# secam-perif94.net
KiCad netlist of a schematic drawn in EAGLE
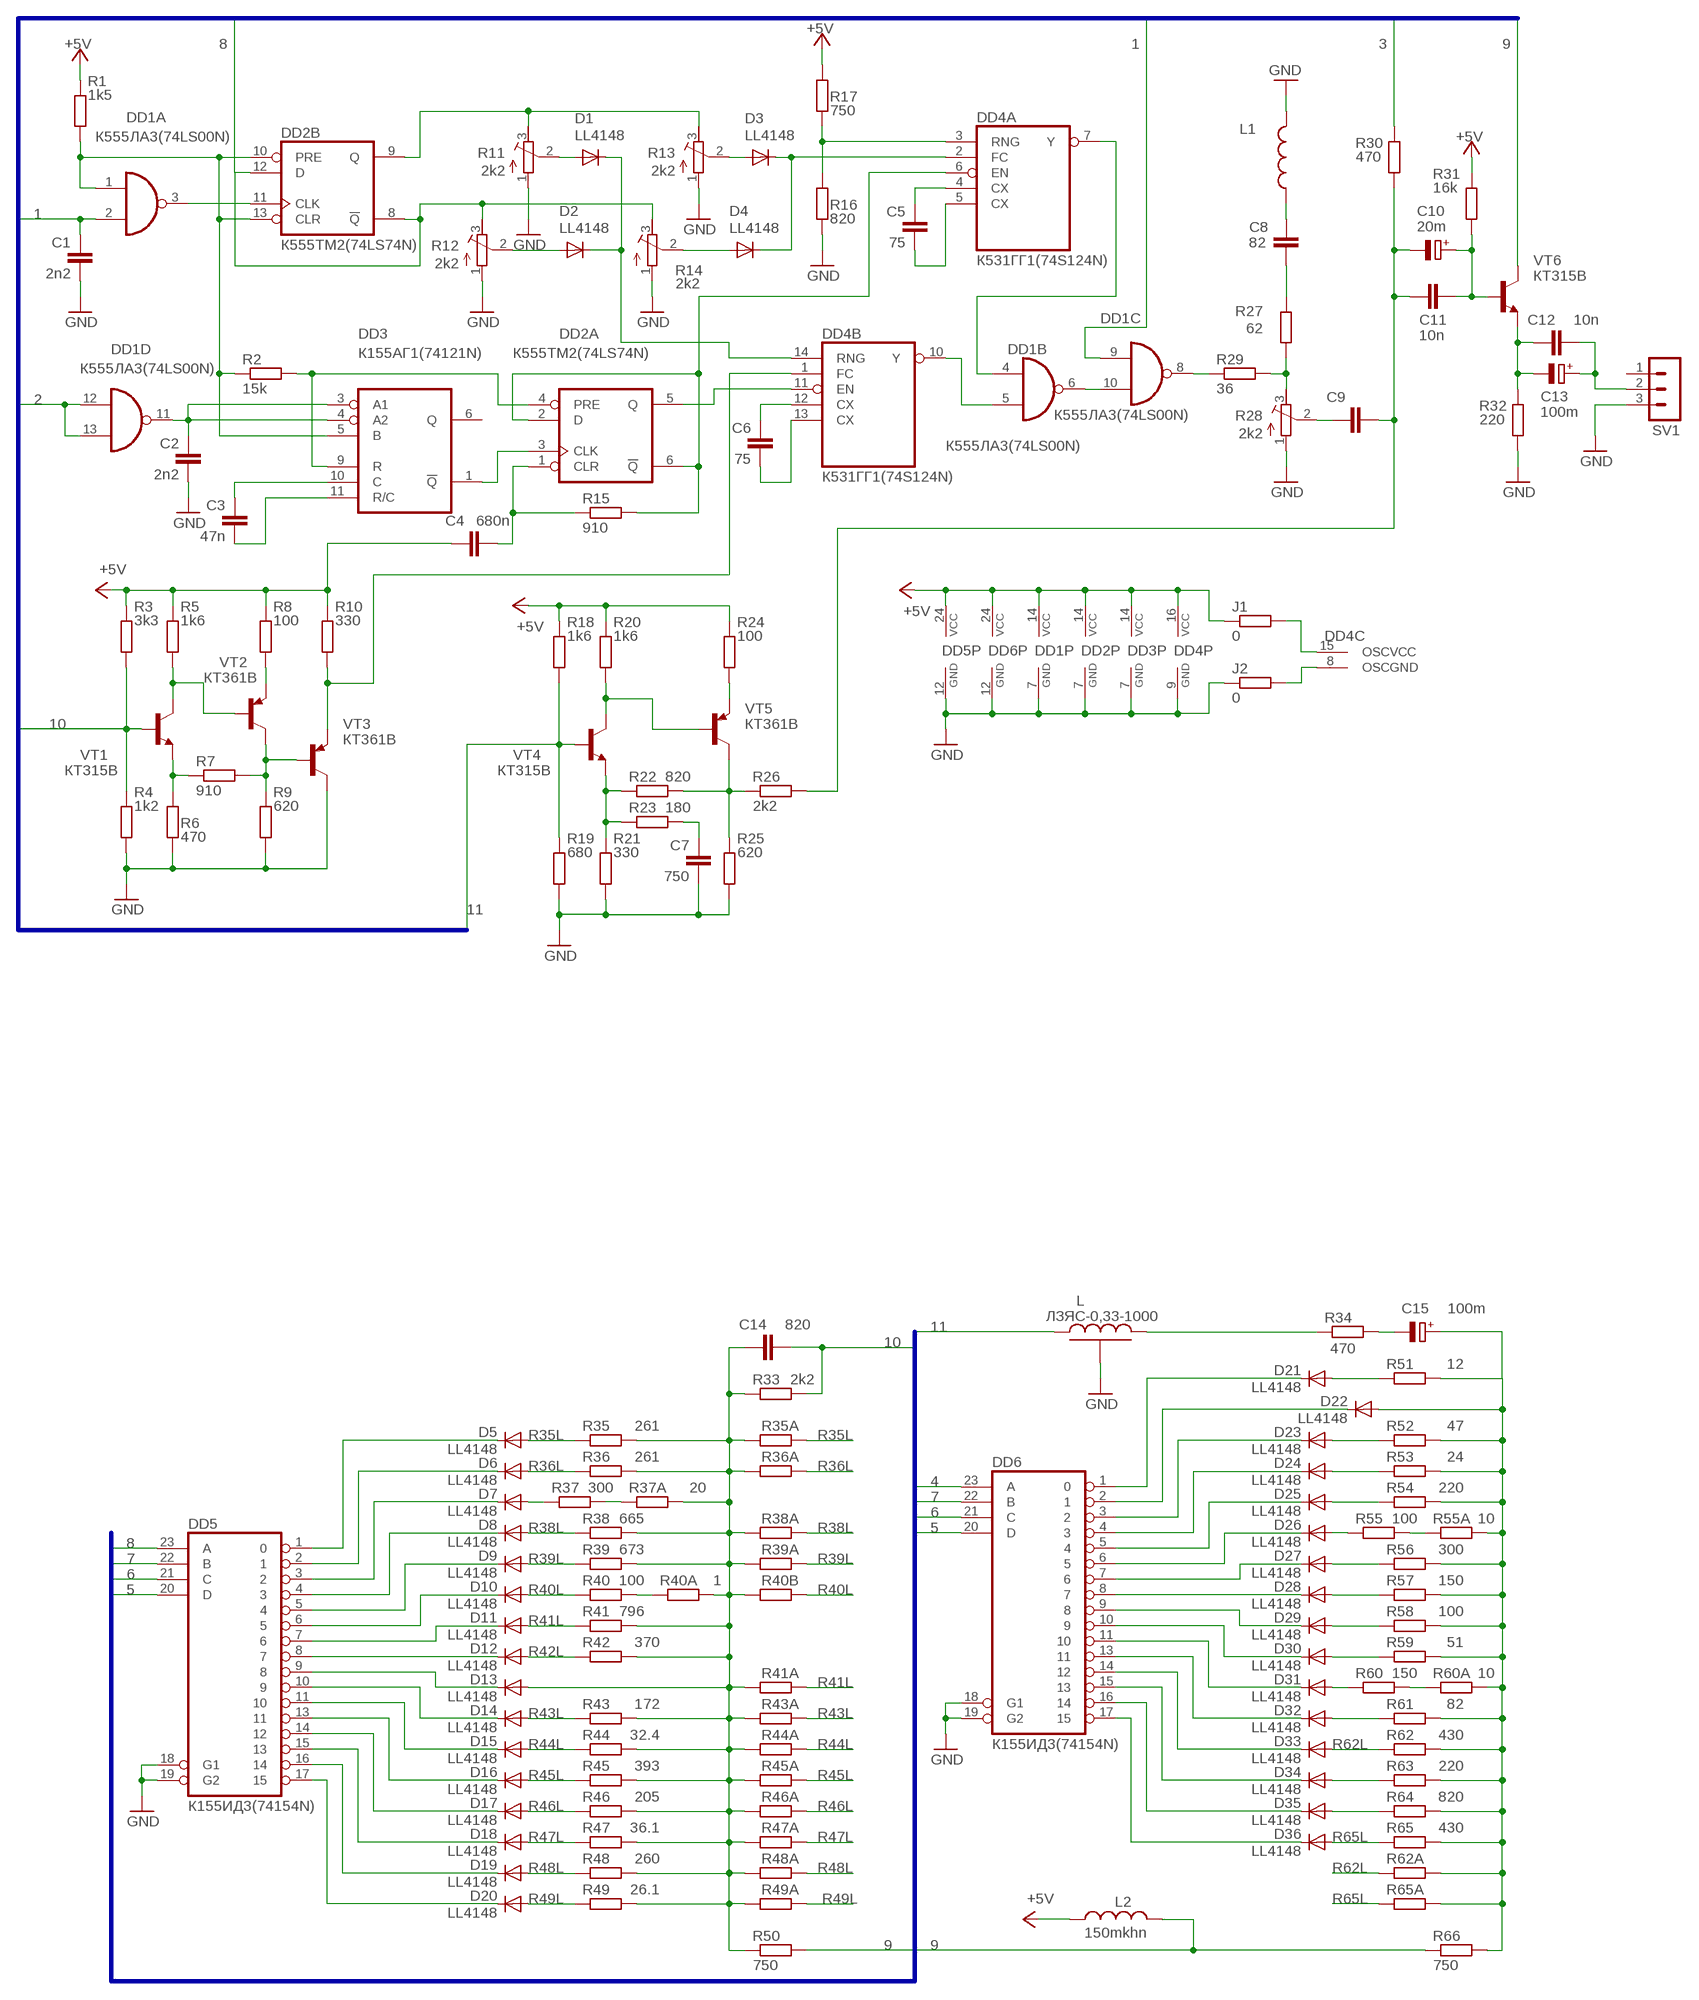
[diagram p0: schematic, sheet 1]

(export (version "E")
  (design (tool "Eeschema 10.0.6"))
  (components
    (comp (ref "C1")
      (value "2n2")
      (footprint "eagle-import:C025-025X050")
      (libsource (lib "eagle-import") (part "C-EU025-025X050"))
    )
    (comp (ref "C2")
      (value "2n2")
      (footprint "eagle-import:C025-025X050")
      (libsource (lib "eagle-import") (part "C-EU025-025X050"))
    )
    (comp (ref "C3")
      (value "47n")
      (footprint "eagle-import:C025-025X050")
      (libsource (lib "eagle-import") (part "C-EU025-025X050"))
    )
    (comp (ref "C4")
      (value "680n")
      (footprint "eagle-import:C025-025X050")
      (libsource (lib "eagle-import") (part "C-EU025-025X050"))
    )
    (comp (ref "C5")
      (value "75")
      (footprint "eagle-import:C025-025X050")
      (libsource (lib "eagle-import") (part "C-EU025-025X050"))
    )
    (comp (ref "C6")
      (value "75")
      (footprint "eagle-import:C025-025X050")
      (libsource (lib "eagle-import") (part "C-EU025-025X050"))
    )
    (comp (ref "C7")
      (value "750")
      (footprint "eagle-import:C025-025X050")
      (libsource (lib "eagle-import") (part "C-EU025-025X050"))
    )
    (comp (ref "C8")
      (value "82")
      (footprint "eagle-import:C025-025X050")
      (libsource (lib "eagle-import") (part "C-EU025-025X050"))
    )
    (comp (ref "C9")
      (value "C-EU025-025X050")
      (footprint "eagle-import:C025-025X050")
      (libsource (lib "eagle-import") (part "C-EU025-025X050"))
    )
    (comp (ref "C10")
      (value "20m")
      (footprint "eagle-import:E2,5-5")
      (libsource (lib "eagle-import") (part "CPOL-EUE2.5-5"))
    )
    (comp (ref "C11")
      (value "10n")
      (footprint "eagle-import:C025-025X050")
      (libsource (lib "eagle-import") (part "C-EU025-025X050"))
    )
    (comp (ref "C12")
      (value "10n")
      (footprint "eagle-import:C025-025X050")
      (libsource (lib "eagle-import") (part "C-EU025-025X050"))
    )
    (comp (ref "C13")
      (value "100m")
      (footprint "eagle-import:E2,5-5")
      (libsource (lib "eagle-import") (part "CPOL-EUE2.5-5"))
    )
    (comp (ref "C14")
      (value "820")
      (footprint "eagle-import:C025-025X050")
      (libsource (lib "eagle-import") (part "C-EU025-025X050"))
    )
    (comp (ref "C15")
      (value "100m")
      (footprint "eagle-import:E2,5-5")
      (libsource (lib "eagle-import") (part "CPOL-EUE2.5-5"))
    )
    (comp (ref "D1")
      (value "LL4148")
      (footprint "eagle-import:SOD80C")
      (libsource (lib "eagle-import") (part "DIODE-SOD80C"))
    )
    (comp (ref "D2")
      (value "LL4148")
      (footprint "eagle-import:SOD80C")
      (libsource (lib "eagle-import") (part "DIODE-SOD80C"))
    )
    (comp (ref "D3")
      (value "LL4148")
      (footprint "eagle-import:SOD80C")
      (libsource (lib "eagle-import") (part "DIODE-SOD80C"))
    )
    (comp (ref "D4")
      (value "LL4148")
      (footprint "eagle-import:SOD80C")
      (libsource (lib "eagle-import") (part "DIODE-SOD80C"))
    )
    (comp (ref "D5")
      (value "LL4148")
      (footprint "eagle-import:SOD80C")
      (libsource (lib "eagle-import") (part "DIODE-SOD80C"))
    )
    (comp (ref "D6")
      (value "LL4148")
      (footprint "eagle-import:SOD80C")
      (libsource (lib "eagle-import") (part "DIODE-SOD80C"))
    )
    (comp (ref "D7")
      (value "LL4148")
      (footprint "eagle-import:SOD80C")
      (libsource (lib "eagle-import") (part "DIODE-SOD80C"))
    )
    (comp (ref "D8")
      (value "LL4148")
      (footprint "eagle-import:SOD80C")
      (libsource (lib "eagle-import") (part "DIODE-SOD80C"))
    )
    (comp (ref "D9")
      (value "LL4148")
      (footprint "eagle-import:SOD80C")
      (libsource (lib "eagle-import") (part "DIODE-SOD80C"))
    )
    (comp (ref "D10")
      (value "LL4148")
      (footprint "eagle-import:SOD80C")
      (libsource (lib "eagle-import") (part "DIODE-SOD80C"))
    )
    (comp (ref "D11")
      (value "LL4148")
      (footprint "eagle-import:SOD80C")
      (libsource (lib "eagle-import") (part "DIODE-SOD80C"))
    )
    (comp (ref "D12")
      (value "LL4148")
      (footprint "eagle-import:SOD80C")
      (libsource (lib "eagle-import") (part "DIODE-SOD80C"))
    )
    (comp (ref "D13")
      (value "LL4148")
      (footprint "eagle-import:SOD80C")
      (libsource (lib "eagle-import") (part "DIODE-SOD80C"))
    )
    (comp (ref "D14")
      (value "LL4148")
      (footprint "eagle-import:SOD80C")
      (libsource (lib "eagle-import") (part "DIODE-SOD80C"))
    )
    (comp (ref "D15")
      (value "LL4148")
      (footprint "eagle-import:SOD80C")
      (libsource (lib "eagle-import") (part "DIODE-SOD80C"))
    )
    (comp (ref "D16")
      (value "LL4148")
      (footprint "eagle-import:SOD80C")
      (libsource (lib "eagle-import") (part "DIODE-SOD80C"))
    )
    (comp (ref "D17")
      (value "LL4148")
      (footprint "eagle-import:SOD80C")
      (libsource (lib "eagle-import") (part "DIODE-SOD80C"))
    )
    (comp (ref "D18")
      (value "LL4148")
      (footprint "eagle-import:SOD80C")
      (libsource (lib "eagle-import") (part "DIODE-SOD80C"))
    )
    (comp (ref "D19")
      (value "LL4148")
      (footprint "eagle-import:SOD80C")
      (libsource (lib "eagle-import") (part "DIODE-SOD80C"))
    )
    (comp (ref "D20")
      (value "LL4148")
      (footprint "eagle-import:SOD80C")
      (libsource (lib "eagle-import") (part "DIODE-SOD80C"))
    )
    (comp (ref "D21")
      (value "LL4148")
      (footprint "eagle-import:SOD80C")
      (libsource (lib "eagle-import") (part "DIODE-SOD80C"))
    )
    (comp (ref "D22")
      (value "LL4148")
      (footprint "eagle-import:SOD80C")
      (libsource (lib "eagle-import") (part "DIODE-SOD80C"))
    )
    (comp (ref "D23")
      (value "LL4148")
      (footprint "eagle-import:SOD80C")
      (libsource (lib "eagle-import") (part "DIODE-SOD80C"))
    )
    (comp (ref "D24")
      (value "LL4148")
      (footprint "eagle-import:SOD80C")
      (libsource (lib "eagle-import") (part "DIODE-SOD80C"))
    )
    (comp (ref "D25")
      (value "LL4148")
      (footprint "eagle-import:SOD80C")
      (libsource (lib "eagle-import") (part "DIODE-SOD80C"))
    )
    (comp (ref "D26")
      (value "LL4148")
      (footprint "eagle-import:SOD80C")
      (libsource (lib "eagle-import") (part "DIODE-SOD80C"))
    )
    (comp (ref "D27")
      (value "LL4148")
      (footprint "eagle-import:SOD80C")
      (libsource (lib "eagle-import") (part "DIODE-SOD80C"))
    )
    (comp (ref "D28")
      (value "LL4148")
      (footprint "eagle-import:SOD80C")
      (libsource (lib "eagle-import") (part "DIODE-SOD80C"))
    )
    (comp (ref "D29")
      (value "LL4148")
      (footprint "eagle-import:SOD80C")
      (libsource (lib "eagle-import") (part "DIODE-SOD80C"))
    )
    (comp (ref "D30")
      (value "LL4148")
      (footprint "eagle-import:SOD80C")
      (libsource (lib "eagle-import") (part "DIODE-SOD80C"))
    )
    (comp (ref "D31")
      (value "LL4148")
      (footprint "eagle-import:SOD80C")
      (libsource (lib "eagle-import") (part "DIODE-SOD80C"))
    )
    (comp (ref "D32")
      (value "LL4148")
      (footprint "eagle-import:SOD80C")
      (libsource (lib "eagle-import") (part "DIODE-SOD80C"))
    )
    (comp (ref "D33")
      (value "LL4148")
      (footprint "eagle-import:SOD80C")
      (libsource (lib "eagle-import") (part "DIODE-SOD80C"))
    )
    (comp (ref "D34")
      (value "LL4148")
      (footprint "eagle-import:SOD80C")
      (libsource (lib "eagle-import") (part "DIODE-SOD80C"))
    )
    (comp (ref "D35")
      (value "LL4148")
      (footprint "eagle-import:SOD80C")
      (libsource (lib "eagle-import") (part "DIODE-SOD80C"))
    )
    (comp (ref "D36")
      (value "LL4148")
      (footprint "eagle-import:SOD80C")
      (libsource (lib "eagle-import") (part "DIODE-SOD80C"))
    )
    (comp (ref "DD1")
      (value "К555ЛА3(74LS00N)")
      (footprint "eagle-import:DIL14")
      (libsource (lib "eagle-import") (part "7400NLS"))
    )
    (comp (ref "DD2")
      (value "К555ТМ2(74LS74N)")
      (footprint "eagle-import:DIL14")
      (libsource (lib "eagle-import") (part "7474NLS"))
    )
    (comp (ref "DD3")
      (value "К155АГ1(74121N)")
      (footprint "eagle-import:DIL14")
      (libsource (lib "eagle-import") (part "74121N"))
    )
    (comp (ref "DD4")
      (value "К531ГГ1(74S124N)")
      (footprint "eagle-import:DIL16")
      (libsource (lib "eagle-import") (part "74124NS"))
    )
    (comp (ref "DD5")
      (value "К155ИД3(74154N)")
      (footprint "eagle-import:DIL24-6")
      (libsource (lib "eagle-import") (part "74154N"))
    )
    (comp (ref "DD6")
      (value "К155ИД3(74154N)")
      (footprint "eagle-import:DIL24-6")
      (libsource (lib "eagle-import") (part "74154N"))
    )
    (comp (ref "J1")
      (value "0")
      (footprint "eagle-import:M0805")
      (libsource (lib "eagle-import") (part "R-EU_M0805"))
    )
    (comp (ref "J2")
      (value "0")
      (footprint "eagle-import:M0805")
      (libsource (lib "eagle-import") (part "R-EU_M0805"))
    )
    (comp (ref "L")
      (value "ЛЗЯС-0,33-1000")
      (footprint "eagle-import:ЛЗЯС-0,33-1000")
      (libsource (lib "eagle-import") (part "ЛЗЯС-0,33-1000"))
    )
    (comp (ref "L1")
      (value "L-US0204/7")
      (footprint "eagle-import:0204_7")
      (libsource (lib "eagle-import") (part "resistor_L-US0204/7"))
    )
    (comp (ref "L2")
      (value "150mkhn")
      (footprint "eagle-import:0207_15")
      (libsource (lib "eagle-import") (part "L-US0207/15"))
    )
    (comp (ref "R1")
      (value "1k5")
      (footprint "eagle-import:M0805")
      (libsource (lib "eagle-import") (part "R-EU_M0805"))
    )
    (comp (ref "R2")
      (value "15k")
      (footprint "eagle-import:M0805")
      (libsource (lib "eagle-import") (part "R-EU_M0805"))
    )
    (comp (ref "R3")
      (value "3k3")
      (footprint "eagle-import:M0805")
      (libsource (lib "eagle-import") (part "R-EU_M0805"))
    )
    (comp (ref "R4")
      (value "1k2")
      (footprint "eagle-import:M0805")
      (libsource (lib "eagle-import") (part "R-EU_M0805"))
    )
    (comp (ref "R5")
      (value "1k6")
      (footprint "eagle-import:M0805")
      (libsource (lib "eagle-import") (part "R-EU_M0805"))
    )
    (comp (ref "R6")
      (value "470")
      (footprint "eagle-import:M0805")
      (libsource (lib "eagle-import") (part "R-EU_M0805"))
    )
    (comp (ref "R7")
      (value "910")
      (footprint "eagle-import:M0805")
      (libsource (lib "eagle-import") (part "R-EU_M0805"))
    )
    (comp (ref "R8")
      (value "100")
      (footprint "eagle-import:M0805")
      (libsource (lib "eagle-import") (part "R-EU_M0805"))
    )
    (comp (ref "R9")
      (value "620")
      (footprint "eagle-import:M0805")
      (libsource (lib "eagle-import") (part "R-EU_M0805"))
    )
    (comp (ref "R10")
      (value "330")
      (footprint "eagle-import:M0805")
      (libsource (lib "eagle-import") (part "R-EU_M0805"))
    )
    (comp (ref "R11")
      (value "2k2")
      (footprint "eagle-import:RTRIM3296W")
      (libsource (lib "eagle-import") (part "R-TRIMM3296W"))
    )
    (comp (ref "R12")
      (value "2k2")
      (footprint "eagle-import:RTRIM3296W")
      (libsource (lib "eagle-import") (part "R-TRIMM3296W"))
    )
    (comp (ref "R13")
      (value "2k2")
      (footprint "eagle-import:RTRIM3296W")
      (libsource (lib "eagle-import") (part "R-TRIMM3296W"))
    )
    (comp (ref "R14")
      (value "2k2")
      (footprint "eagle-import:RTRIM3296W")
      (libsource (lib "eagle-import") (part "R-TRIMM3296W"))
    )
    (comp (ref "R15")
      (value "910")
      (footprint "eagle-import:M0805")
      (libsource (lib "eagle-import") (part "R-EU_M0805"))
    )
    (comp (ref "R16")
      (value "820")
      (footprint "eagle-import:M0805")
      (libsource (lib "eagle-import") (part "R-EU_M0805"))
    )
    (comp (ref "R17")
      (value "750")
      (footprint "eagle-import:M0805")
      (libsource (lib "eagle-import") (part "R-EU_M0805"))
    )
    (comp (ref "R18")
      (value "1k6")
      (footprint "eagle-import:M0805")
      (libsource (lib "eagle-import") (part "R-EU_M0805"))
    )
    (comp (ref "R19")
      (value "680")
      (footprint "eagle-import:M0805")
      (libsource (lib "eagle-import") (part "R-EU_M0805"))
    )
    (comp (ref "R20")
      (value "1k6")
      (footprint "eagle-import:M0805")
      (libsource (lib "eagle-import") (part "R-EU_M0805"))
    )
    (comp (ref "R21")
      (value "330")
      (footprint "eagle-import:M0805")
      (libsource (lib "eagle-import") (part "R-EU_M0805"))
    )
    (comp (ref "R22")
      (value "820")
      (footprint "eagle-import:M0805")
      (libsource (lib "eagle-import") (part "R-EU_M0805"))
    )
    (comp (ref "R23")
      (value "180")
      (footprint "eagle-import:M0805")
      (libsource (lib "eagle-import") (part "R-EU_M0805"))
    )
    (comp (ref "R24")
      (value "100")
      (footprint "eagle-import:M0805")
      (libsource (lib "eagle-import") (part "R-EU_M0805"))
    )
    (comp (ref "R25")
      (value "620")
      (footprint "eagle-import:M0805")
      (libsource (lib "eagle-import") (part "R-EU_M0805"))
    )
    (comp (ref "R26")
      (value "2k2")
      (footprint "eagle-import:M0805")
      (libsource (lib "eagle-import") (part "R-EU_M0805"))
    )
    (comp (ref "R27")
      (value "62")
      (footprint "eagle-import:M0805")
      (libsource (lib "eagle-import") (part "R-EU_M0805"))
    )
    (comp (ref "R28")
      (value "2k2")
      (footprint "eagle-import:RTRIM3296W")
      (libsource (lib "eagle-import") (part "R-TRIMM3296W"))
    )
    (comp (ref "R29")
      (value "36")
      (footprint "eagle-import:M0805")
      (libsource (lib "eagle-import") (part "R-EU_M0805"))
    )
    (comp (ref "R30")
      (value "470")
      (footprint "eagle-import:M0805")
      (libsource (lib "eagle-import") (part "R-EU_M0805"))
    )
    (comp (ref "R31")
      (value "16k")
      (footprint "eagle-import:M0805")
      (libsource (lib "eagle-import") (part "R-EU_M0805"))
    )
    (comp (ref "R32")
      (value "220")
      (footprint "eagle-import:M0805")
      (libsource (lib "eagle-import") (part "R-EU_M0805"))
    )
    (comp (ref "R33")
      (value "2k2")
      (footprint "eagle-import:M0805")
      (libsource (lib "eagle-import") (part "R-EU_M0805"))
    )
    (comp (ref "R34")
      (value "470")
      (footprint "eagle-import:M0805")
      (libsource (lib "eagle-import") (part "R-EU_M0805"))
    )
    (comp (ref "R35")
      (value "261")
      (footprint "eagle-import:M0805")
      (libsource (lib "eagle-import") (part "R-EU_M0805"))
    )
    (comp (ref "R35A")
      (value "R-EU_0207/10")
      (footprint "eagle-import:0207_10")
      (libsource (lib "eagle-import") (part "R-EU_0207/10"))
    )
    (comp (ref "R36")
      (value "261")
      (footprint "eagle-import:M0805")
      (libsource (lib "eagle-import") (part "R-EU_M0805"))
    )
    (comp (ref "R36A")
      (value "R-EU_0207/10")
      (footprint "eagle-import:0207_10")
      (libsource (lib "eagle-import") (part "R-EU_0207/10"))
    )
    (comp (ref "R37")
      (value "300")
      (footprint "eagle-import:M0805")
      (libsource (lib "eagle-import") (part "R-EU_M0805"))
    )
    (comp (ref "R37A")
      (value "20")
      (footprint "eagle-import:M0805")
      (libsource (lib "eagle-import") (part "R-EU_M0805"))
    )
    (comp (ref "R38")
      (value "665")
      (footprint "eagle-import:M0805")
      (libsource (lib "eagle-import") (part "R-EU_M0805"))
    )
    (comp (ref "R38A")
      (value "R-EU_0207/10")
      (footprint "eagle-import:0207_10")
      (libsource (lib "eagle-import") (part "R-EU_0207/10"))
    )
    (comp (ref "R39")
      (value "673")
      (footprint "eagle-import:M0805")
      (libsource (lib "eagle-import") (part "R-EU_M0805"))
    )
    (comp (ref "R39A")
      (value "R-EU_0207/10")
      (footprint "eagle-import:0207_10")
      (libsource (lib "eagle-import") (part "R-EU_0207/10"))
    )
    (comp (ref "R40")
      (value "100")
      (footprint "eagle-import:M0805")
      (libsource (lib "eagle-import") (part "R-EU_M0805"))
    )
    (comp (ref "R40A")
      (value "1")
      (footprint "eagle-import:M0805")
      (libsource (lib "eagle-import") (part "R-EU_M0805"))
    )
    (comp (ref "R40B")
      (value "R-EU_0207/10")
      (footprint "eagle-import:0207_10")
      (libsource (lib "eagle-import") (part "R-EU_0207/10"))
    )
    (comp (ref "R41")
      (value "796")
      (footprint "eagle-import:M0805")
      (libsource (lib "eagle-import") (part "R-EU_M0805"))
    )
    (comp (ref "R41A")
      (value "R-EU_0207/10")
      (footprint "eagle-import:0207_10")
      (libsource (lib "eagle-import") (part "R-EU_0207/10"))
    )
    (comp (ref "R42")
      (value "370")
      (footprint "eagle-import:M0805")
      (libsource (lib "eagle-import") (part "R-EU_M0805"))
    )
    (comp (ref "R43")
      (value "172")
      (footprint "eagle-import:M0805")
      (libsource (lib "eagle-import") (part "R-EU_M0805"))
    )
    (comp (ref "R43A")
      (value "R-EU_0207/10")
      (footprint "eagle-import:0207_10")
      (libsource (lib "eagle-import") (part "R-EU_0207/10"))
    )
    (comp (ref "R44")
      (value "32.4")
      (footprint "eagle-import:M0805")
      (libsource (lib "eagle-import") (part "R-EU_M0805"))
    )
    (comp (ref "R44A")
      (value "R-EU_0207/10")
      (footprint "eagle-import:0207_10")
      (libsource (lib "eagle-import") (part "R-EU_0207/10"))
    )
    (comp (ref "R45")
      (value "393")
      (footprint "eagle-import:M0805")
      (libsource (lib "eagle-import") (part "R-EU_M0805"))
    )
    (comp (ref "R45A")
      (value "R-EU_0207/10")
      (footprint "eagle-import:0207_10")
      (libsource (lib "eagle-import") (part "R-EU_0207/10"))
    )
    (comp (ref "R46")
      (value "205")
      (footprint "eagle-import:M0805")
      (libsource (lib "eagle-import") (part "R-EU_M0805"))
    )
    (comp (ref "R46A")
      (value "R-EU_0207/10")
      (footprint "eagle-import:0207_10")
      (libsource (lib "eagle-import") (part "R-EU_0207/10"))
    )
    (comp (ref "R47")
      (value "36.1")
      (footprint "eagle-import:M0805")
      (libsource (lib "eagle-import") (part "R-EU_M0805"))
    )
    (comp (ref "R47A")
      (value "R-EU_0207/10")
      (footprint "eagle-import:0207_10")
      (libsource (lib "eagle-import") (part "R-EU_0207/10"))
    )
    (comp (ref "R48")
      (value "260")
      (footprint "eagle-import:M0805")
      (libsource (lib "eagle-import") (part "R-EU_M0805"))
    )
    (comp (ref "R48A")
      (value "R-EU_0207/10")
      (footprint "eagle-import:0207_10")
      (libsource (lib "eagle-import") (part "R-EU_0207/10"))
    )
    (comp (ref "R49")
      (value "26.1")
      (footprint "eagle-import:M0805")
      (libsource (lib "eagle-import") (part "R-EU_M0805"))
    )
    (comp (ref "R49A")
      (value "R-EU_0207/10")
      (footprint "eagle-import:0207_10")
      (libsource (lib "eagle-import") (part "R-EU_0207/10"))
    )
    (comp (ref "R50")
      (value "750")
      (footprint "eagle-import:M0805")
      (libsource (lib "eagle-import") (part "R-EU_M0805"))
    )
    (comp (ref "R51")
      (value "12")
      (footprint "eagle-import:M0805")
      (libsource (lib "eagle-import") (part "R-EU_M0805"))
    )
    (comp (ref "R52")
      (value "47")
      (footprint "eagle-import:M0805")
      (libsource (lib "eagle-import") (part "R-EU_M0805"))
    )
    (comp (ref "R53")
      (value "24")
      (footprint "eagle-import:M0805")
      (libsource (lib "eagle-import") (part "R-EU_M0805"))
    )
    (comp (ref "R54")
      (value "220")
      (footprint "eagle-import:M0805")
      (libsource (lib "eagle-import") (part "R-EU_M0805"))
    )
    (comp (ref "R55")
      (value "100")
      (footprint "eagle-import:M0805")
      (libsource (lib "eagle-import") (part "R-EU_M0805"))
    )
    (comp (ref "R55A")
      (value "10")
      (footprint "eagle-import:M0805")
      (libsource (lib "eagle-import") (part "R-EU_M0805"))
    )
    (comp (ref "R56")
      (value "300")
      (footprint "eagle-import:M0805")
      (libsource (lib "eagle-import") (part "R-EU_M0805"))
    )
    (comp (ref "R57")
      (value "150")
      (footprint "eagle-import:M0805")
      (libsource (lib "eagle-import") (part "R-EU_M0805"))
    )
    (comp (ref "R58")
      (value "100")
      (footprint "eagle-import:M0805")
      (libsource (lib "eagle-import") (part "R-EU_M0805"))
    )
    (comp (ref "R59")
      (value "51")
      (footprint "eagle-import:M0805")
      (libsource (lib "eagle-import") (part "R-EU_M0805"))
    )
    (comp (ref "R60")
      (value "150")
      (footprint "eagle-import:M0805")
      (libsource (lib "eagle-import") (part "R-EU_M0805"))
    )
    (comp (ref "R60A")
      (value "10")
      (footprint "eagle-import:M0805")
      (libsource (lib "eagle-import") (part "R-EU_M0805"))
    )
    (comp (ref "R61")
      (value "82")
      (footprint "eagle-import:M0805")
      (libsource (lib "eagle-import") (part "R-EU_M0805"))
    )
    (comp (ref "R62")
      (value "430")
      (footprint "eagle-import:M0805")
      (libsource (lib "eagle-import") (part "R-EU_M0805"))
    )
    (comp (ref "R62A")
      (value "R-EU_0207/10")
      (footprint "eagle-import:0207_10")
      (libsource (lib "eagle-import") (part "R-EU_0207/10"))
    )
    (comp (ref "R63")
      (value "220")
      (footprint "eagle-import:M0805")
      (libsource (lib "eagle-import") (part "R-EU_M0805"))
    )
    (comp (ref "R64")
      (value "820")
      (footprint "eagle-import:M0805")
      (libsource (lib "eagle-import") (part "R-EU_M0805"))
    )
    (comp (ref "R65")
      (value "430")
      (footprint "eagle-import:M0805")
      (libsource (lib "eagle-import") (part "R-EU_M0805"))
    )
    (comp (ref "R65A")
      (value "R-EU_0207/10")
      (footprint "eagle-import:0207_10")
      (libsource (lib "eagle-import") (part "R-EU_0207/10"))
    )
    (comp (ref "R66")
      (value "750")
      (footprint "eagle-import:M0805")
      (libsource (lib "eagle-import") (part "R-EU_M0805"))
    )
    (comp (ref "SV1")
      (value "MA03-1")
      (footprint "eagle-import:MA03-1")
      (libsource (lib "eagle-import") (part "MA03-1"))
    )
    (comp (ref "VT1")
      (value "КТ315В")
      (footprint "eagle-import:TO92-ECB")
      (libsource (lib "eagle-import") (part "-NPN-TO92-ECB"))
    )
    (comp (ref "VT2")
      (value "КТ361В")
      (footprint "eagle-import:TO92-BCE")
      (libsource (lib "eagle-import") (part "BF421"))
    )
    (comp (ref "VT3")
      (value "КТ361В")
      (footprint "eagle-import:TO92-BCE")
      (libsource (lib "eagle-import") (part "BF421"))
    )
    (comp (ref "VT4")
      (value "КТ315В")
      (footprint "eagle-import:TO92-ECB")
      (libsource (lib "eagle-import") (part "-NPN-TO92-ECB"))
    )
    (comp (ref "VT5")
      (value "КТ361В")
      (footprint "eagle-import:TO92-BCE")
      (libsource (lib "eagle-import") (part "BF421"))
    )
    (comp (ref "VT6")
      (value "КТ315В")
      (footprint "eagle-import:TO92-ECB")
      (libsource (lib "eagle-import") (part "-NPN-TO92-ECB"))
    )
  )
  (nets
    (net (code "1") (name "+5V") (class "Default")
      (node (ref "C4") (pin "1") (pinfunction "1_1") (pintype "passive"))
      (node (ref "DD1") (pin "14") (pinfunction "VCC_14") (pintype "power_in"))
      (node (ref "DD2") (pin "14") (pinfunction "VCC_14") (pintype "power_in"))
      (node (ref "DD3") (pin "14") (pinfunction "VCC_14") (pintype "power_in"))
      (node (ref "DD4") (pin "16") (pinfunction "VCC_16") (pintype "power_in"))
      (node (ref "DD5") (pin "24") (pinfunction "VCC_24") (pintype "power_in"))
      (node (ref "DD6") (pin "24") (pinfunction "VCC_24") (pintype "power_in"))
      (node (ref "J1") (pin "1") (pinfunction "1_1") (pintype "passive"))
      (node (ref "L2") (pin "1") (pinfunction "1_1") (pintype "passive"))
      (node (ref "R1") (pin "2") (pinfunction "2_2") (pintype "passive"))
      (node (ref "R10") (pin "2") (pinfunction "2_2") (pintype "passive"))
      (node (ref "R17") (pin "2") (pinfunction "2_2") (pintype "passive"))
      (node (ref "R18") (pin "2") (pinfunction "2_2") (pintype "passive"))
      (node (ref "R20") (pin "2") (pinfunction "2_2") (pintype "passive"))
      (node (ref "R24") (pin "2") (pinfunction "2_2") (pintype "passive"))
      (node (ref "R3") (pin "2") (pinfunction "2_2") (pintype "passive"))
      (node (ref "R31") (pin "2") (pinfunction "2_2") (pintype "passive"))
      (node (ref "R5") (pin "2") (pinfunction "2_2") (pintype "passive"))
      (node (ref "R8") (pin "2") (pinfunction "2_2") (pintype "passive"))
    )
    (net (code "2") (name "/1") (class "Default")
      (node (ref "C1") (pin "1") (pinfunction "1_1") (pintype "passive"))
      (node (ref "DD1") (pin "2") (pinfunction "I1_2") (pintype "input"))
      (node (ref "DD1") (pin "9") (pinfunction "I0_9") (pintype "input"))
    )
    (net (code "3") (name "/2") (class "Default")
      (node (ref "DD1") (pin "12") (pinfunction "I0_12") (pintype "input"))
      (node (ref "DD1") (pin "13") (pinfunction "I1_13") (pintype "input"))
    )
    (net (code "4") (name "/3") (class "Default")
      (node (ref "R30") (pin "2") (pinfunction "2_2") (pintype "passive"))
    )
    (net (code "5") (name "/4") (class "Default")
      (node (ref "DD6") (pin "23") (pinfunction "A_23") (pintype "input"))
    )
    (net (code "6") (name "/5") (class "Default")
      (node (ref "DD5") (pin "20") (pinfunction "D_20") (pintype "input"))
      (node (ref "DD6") (pin "20") (pinfunction "D_20") (pintype "input"))
    )
    (net (code "7") (name "/6") (class "Default")
      (node (ref "DD5") (pin "21") (pinfunction "C_21") (pintype "input"))
      (node (ref "DD6") (pin "21") (pinfunction "C_21") (pintype "input"))
    )
    (net (code "8") (name "/7") (class "Default")
      (node (ref "DD5") (pin "22") (pinfunction "B_22") (pintype "input"))
      (node (ref "DD6") (pin "22") (pinfunction "B_22") (pintype "input"))
    )
    (net (code "9") (name "/8") (class "Default")
      (node (ref "DD2") (pin "12") (pinfunction "D_12") (pintype "input"))
      (node (ref "DD2") (pin "8") (pinfunction "~{Q}_8") (pintype "output"))
      (node (ref "DD5") (pin "23") (pinfunction "A_23") (pintype "input"))
      (node (ref "R12") (pin "3") (pinfunction "A_3") (pintype "passive"))
      (node (ref "R14") (pin "3") (pinfunction "A_3") (pintype "passive"))
    )
    (net (code "10") (name "/9") (class "Default")
      (node (ref "L2") (pin "2") (pinfunction "2_2") (pintype "passive"))
      (node (ref "R50") (pin "2") (pinfunction "2_2") (pintype "passive"))
      (node (ref "R66") (pin "1") (pinfunction "1_1") (pintype "passive"))
      (node (ref "VT6") (pin "C") (pinfunction "C_C") (pintype "passive"))
    )
    (net (code "11") (name "/10") (class "Default")
      (node (ref "C14") (pin "2") (pinfunction "2_2") (pintype "passive"))
      (node (ref "R3") (pin "1") (pinfunction "1_1") (pintype "passive"))
      (node (ref "R33") (pin "2") (pinfunction "2_2") (pintype "passive"))
      (node (ref "R4") (pin "2") (pinfunction "2_2") (pintype "passive"))
      (node (ref "VT1") (pin "B") (pinfunction "B_B") (pintype "passive"))
    )
    (net (code "12") (name "/11") (class "Default")
      (node (ref "L") (pin "1") (pinfunction "1_1") (pintype "bidirectional"))
      (node (ref "R18") (pin "1") (pinfunction "1_1") (pintype "passive"))
      (node (ref "R19") (pin "2") (pinfunction "2_2") (pintype "passive"))
      (node (ref "VT4") (pin "B") (pinfunction "B_B") (pintype "passive"))
    )
    (net (code "13") (name "/R35L") (class "Default")
      (node (ref "D5") (pin "A") (pinfunction "A_A") (pintype "passive"))
      (node (ref "R35") (pin "1") (pinfunction "1_1") (pintype "passive"))
      (node (ref "R35A") (pin "1") (pinfunction "1_1") (pintype "passive"))
    )
    (net (code "14") (name "/R36L") (class "Default")
      (node (ref "D6") (pin "A") (pinfunction "A_A") (pintype "passive"))
      (node (ref "R36") (pin "1") (pinfunction "1_1") (pintype "passive"))
      (node (ref "R36A") (pin "1") (pinfunction "1_1") (pintype "passive"))
    )
    (net (code "15") (name "/R38L") (class "Default")
      (node (ref "D8") (pin "A") (pinfunction "A_A") (pintype "passive"))
      (node (ref "R38") (pin "1") (pinfunction "1_1") (pintype "passive"))
      (node (ref "R38A") (pin "1") (pinfunction "1_1") (pintype "passive"))
    )
    (net (code "16") (name "/R39L") (class "Default")
      (node (ref "D9") (pin "A") (pinfunction "A_A") (pintype "passive"))
      (node (ref "R39") (pin "1") (pinfunction "1_1") (pintype "passive"))
      (node (ref "R39A") (pin "1") (pinfunction "1_1") (pintype "passive"))
    )
    (net (code "17") (name "/R40L") (class "Default")
      (node (ref "D10") (pin "A") (pinfunction "A_A") (pintype "passive"))
      (node (ref "R40") (pin "1") (pinfunction "1_1") (pintype "passive"))
      (node (ref "R40B") (pin "1") (pinfunction "1_1") (pintype "passive"))
    )
    (net (code "18") (name "/R41L") (class "Default")
      (node (ref "D11") (pin "A") (pinfunction "A_A") (pintype "passive"))
      (node (ref "R41") (pin "1") (pinfunction "1_1") (pintype "passive"))
      (node (ref "R41A") (pin "1") (pinfunction "1_1") (pintype "passive"))
    )
    (net (code "19") (name "/R42L") (class "Default")
      (node (ref "D12") (pin "A") (pinfunction "A_A") (pintype "passive"))
      (node (ref "R42") (pin "1") (pinfunction "1_1") (pintype "passive"))
    )
    (net (code "20") (name "/R43L") (class "Default")
      (node (ref "D14") (pin "A") (pinfunction "A_A") (pintype "passive"))
      (node (ref "R43") (pin "1") (pinfunction "1_1") (pintype "passive"))
      (node (ref "R43A") (pin "1") (pinfunction "1_1") (pintype "passive"))
    )
    (net (code "21") (name "/R44L") (class "Default")
      (node (ref "D15") (pin "A") (pinfunction "A_A") (pintype "passive"))
      (node (ref "R44") (pin "1") (pinfunction "1_1") (pintype "passive"))
      (node (ref "R44A") (pin "1") (pinfunction "1_1") (pintype "passive"))
    )
    (net (code "22") (name "/R45L") (class "Default")
      (node (ref "D16") (pin "A") (pinfunction "A_A") (pintype "passive"))
      (node (ref "R45") (pin "1") (pinfunction "1_1") (pintype "passive"))
      (node (ref "R45A") (pin "1") (pinfunction "1_1") (pintype "passive"))
    )
    (net (code "23") (name "/R46L") (class "Default")
      (node (ref "D17") (pin "A") (pinfunction "A_A") (pintype "passive"))
      (node (ref "R46") (pin "1") (pinfunction "1_1") (pintype "passive"))
      (node (ref "R46A") (pin "1") (pinfunction "1_1") (pintype "passive"))
    )
    (net (code "24") (name "/R47L") (class "Default")
      (node (ref "D18") (pin "A") (pinfunction "A_A") (pintype "passive"))
      (node (ref "R47") (pin "1") (pinfunction "1_1") (pintype "passive"))
      (node (ref "R47A") (pin "1") (pinfunction "1_1") (pintype "passive"))
    )
    (net (code "25") (name "/R48L") (class "Default")
      (node (ref "D19") (pin "A") (pinfunction "A_A") (pintype "passive"))
      (node (ref "R48") (pin "1") (pinfunction "1_1") (pintype "passive"))
      (node (ref "R48A") (pin "1") (pinfunction "1_1") (pintype "passive"))
    )
    (net (code "26") (name "/R49L") (class "Default")
      (node (ref "D20") (pin "A") (pinfunction "A_A") (pintype "passive"))
      (node (ref "R49") (pin "1") (pinfunction "1_1") (pintype "passive"))
      (node (ref "R49A") (pin "1") (pinfunction "1_1") (pintype "passive"))
    )
    (net (code "27") (name "/R62L") (class "Default")
      (node (ref "D33") (pin "A") (pinfunction "A_A") (pintype "passive"))
      (node (ref "R62") (pin "1") (pinfunction "1_1") (pintype "passive"))
      (node (ref "R62A") (pin "1") (pinfunction "1_1") (pintype "passive"))
    )
    (net (code "28") (name "/R65L") (class "Default")
      (node (ref "D36") (pin "A") (pinfunction "A_A") (pintype "passive"))
      (node (ref "R65") (pin "1") (pinfunction "1_1") (pintype "passive"))
      (node (ref "R65A") (pin "1") (pinfunction "1_1") (pintype "passive"))
    )
    (net (code "29") (name "GND") (class "Default")
      (node (ref "C1") (pin "2") (pinfunction "2_2") (pintype "passive"))
      (node (ref "C2") (pin "2") (pinfunction "2_2") (pintype "passive"))
      (node (ref "C7") (pin "2") (pinfunction "2_2") (pintype "passive"))
      (node (ref "DD1") (pin "7") (pinfunction "GND_7") (pintype "power_in"))
      (node (ref "DD2") (pin "7") (pinfunction "GND_7") (pintype "power_in"))
      (node (ref "DD3") (pin "7") (pinfunction "GND_7") (pintype "power_in"))
      (node (ref "DD4") (pin "9") (pinfunction "GND_9") (pintype "power_in"))
      (node (ref "DD5") (pin "12") (pinfunction "GND_12") (pintype "power_in"))
      (node (ref "DD5") (pin "18") (pinfunction "G1_18") (pintype "input"))
      (node (ref "DD5") (pin "19") (pinfunction "G2_19") (pintype "input"))
      (node (ref "DD6") (pin "12") (pinfunction "GND_12") (pintype "power_in"))
      (node (ref "DD6") (pin "18") (pinfunction "G1_18") (pintype "input"))
      (node (ref "DD6") (pin "19") (pinfunction "G2_19") (pintype "input"))
      (node (ref "J2") (pin "1") (pinfunction "1_1") (pintype "passive"))
      (node (ref "L") (pin "G") (pinfunction "G_G") (pintype "bidirectional"))
      (node (ref "L1") (pin "2") (pinfunction "2_2") (pintype "passive"))
      (node (ref "R11") (pin "1") (pinfunction "E_1") (pintype "passive"))
      (node (ref "R12") (pin "1") (pinfunction "E_1") (pintype "passive"))
      (node (ref "R13") (pin "1") (pinfunction "E_1") (pintype "passive"))
      (node (ref "R14") (pin "1") (pinfunction "E_1") (pintype "passive"))
      (node (ref "R16") (pin "1") (pinfunction "1_1") (pintype "passive"))
      (node (ref "R19") (pin "1") (pinfunction "1_1") (pintype "passive"))
      (node (ref "R21") (pin "1") (pinfunction "1_1") (pintype "passive"))
      (node (ref "R25") (pin "1") (pinfunction "1_1") (pintype "passive"))
      (node (ref "R28") (pin "1") (pinfunction "E_1") (pintype "passive"))
      (node (ref "R32") (pin "1") (pinfunction "1_1") (pintype "passive"))
      (node (ref "R4") (pin "1") (pinfunction "1_1") (pintype "passive"))
      (node (ref "R6") (pin "1") (pinfunction "1_1") (pintype "passive"))
      (node (ref "R9") (pin "1") (pinfunction "1_1") (pintype "passive"))
      (node (ref "SV1") (pin "3") (pinfunction "3_3") (pintype "passive"))
      (node (ref "VT3") (pin "C") (pinfunction "C_C") (pintype "passive"))
    )
    (net (code "30") (name "Net-(C5-Pad1)") (class "Default")
      (node (ref "C5") (pin "1") (pinfunction "1_1") (pintype "passive"))
      (node (ref "DD4") (pin "4") (pinfunction "CX_4") (pintype "input"))
    )
    (net (code "31") (name "Net-(C5-Pad2)") (class "Default")
      (node (ref "C5") (pin "2") (pinfunction "2_2") (pintype "passive"))
      (node (ref "DD4") (pin "5") (pinfunction "CX_5") (pintype "input"))
    )
    (net (code "32") (name "Net-(C6-Pad1)") (class "Default")
      (node (ref "C6") (pin "1") (pinfunction "1_1") (pintype "passive"))
      (node (ref "DD4") (pin "12") (pinfunction "CX_12") (pintype "input"))
    )
    (net (code "33") (name "Net-(C6-Pad2)") (class "Default")
      (node (ref "C6") (pin "2") (pinfunction "2_2") (pintype "passive"))
      (node (ref "DD4") (pin "13") (pinfunction "CX_13") (pintype "input"))
    )
    (net (code "34") (name "Net-(C7-Pad1)") (class "Default")
      (node (ref "C7") (pin "1") (pinfunction "1_1") (pintype "passive"))
      (node (ref "R23") (pin "2") (pinfunction "2_2") (pintype "passive"))
    )
    (net (code "35") (name "Net-(C8-Pad1)") (class "Default")
      (node (ref "C8") (pin "1") (pinfunction "1_1") (pintype "passive"))
      (node (ref "R27") (pin "2") (pinfunction "2_2") (pintype "passive"))
    )
    (net (code "36") (name "Net-(C8-Pad2)") (class "Default")
      (node (ref "C8") (pin "2") (pinfunction "2_2") (pintype "passive"))
      (node (ref "L1") (pin "1") (pinfunction "1_1") (pintype "passive"))
    )
    (net (code "37") (name "Net-(C10-Pad+)") (class "Default")
      (node (ref "C10") (pin "+") (pinfunction "+_+") (pintype "passive"))
      (node (ref "C11") (pin "2") (pinfunction "2_2") (pintype "passive"))
      (node (ref "R31") (pin "1") (pinfunction "1_1") (pintype "passive"))
      (node (ref "VT6") (pin "B") (pinfunction "B_B") (pintype "passive"))
    )
    (net (code "38") (name "Net-(C10-Pad-)") (class "Default")
      (node (ref "C10") (pin "-") (pinfunction "-_-") (pintype "passive"))
      (node (ref "C11") (pin "1") (pinfunction "1_1") (pintype "passive"))
      (node (ref "C9") (pin "2") (pinfunction "2_2") (pintype "passive"))
      (node (ref "R26") (pin "2") (pinfunction "2_2") (pintype "passive"))
      (node (ref "R30") (pin "1") (pinfunction "1_1") (pintype "passive"))
    )
    (net (code "39") (name "Net-(C12-Pad1)") (class "Default")
      (node (ref "C12") (pin "1") (pinfunction "1_1") (pintype "passive"))
      (node (ref "C13") (pin "-") (pinfunction "-_-") (pintype "passive"))
      (node (ref "R32") (pin "2") (pinfunction "2_2") (pintype "passive"))
      (node (ref "VT6") (pin "E") (pinfunction "E_E") (pintype "passive"))
    )
    (net (code "40") (name "Net-(C12-Pad2)") (class "Default")
      (node (ref "C12") (pin "2") (pinfunction "2_2") (pintype "passive"))
      (node (ref "C13") (pin "+") (pinfunction "+_+") (pintype "passive"))
      (node (ref "SV1") (pin "2") (pinfunction "2_2") (pintype "passive"))
    )
    (net (code "41") (name "Net-(C14-Pad1)") (class "Default")
      (node (ref "C14") (pin "1") (pinfunction "1_1") (pintype "passive"))
      (node (ref "D13") (pin "A") (pinfunction "A_A") (pintype "passive"))
      (node (ref "R33") (pin "1") (pinfunction "1_1") (pintype "passive"))
      (node (ref "R35") (pin "2") (pinfunction "2_2") (pintype "passive"))
      (node (ref "R35A") (pin "2") (pinfunction "2_2") (pintype "passive"))
      (node (ref "R36") (pin "2") (pinfunction "2_2") (pintype "passive"))
      (node (ref "R36A") (pin "2") (pinfunction "2_2") (pintype "passive"))
      (node (ref "R37A") (pin "2") (pinfunction "2_2") (pintype "passive"))
      (node (ref "R38") (pin "2") (pinfunction "2_2") (pintype "passive"))
      (node (ref "R38A") (pin "2") (pinfunction "2_2") (pintype "passive"))
      (node (ref "R39") (pin "2") (pinfunction "2_2") (pintype "passive"))
      (node (ref "R39A") (pin "2") (pinfunction "2_2") (pintype "passive"))
      (node (ref "R40A") (pin "2") (pinfunction "2_2") (pintype "passive"))
      (node (ref "R40B") (pin "2") (pinfunction "2_2") (pintype "passive"))
      (node (ref "R41") (pin "2") (pinfunction "2_2") (pintype "passive"))
      (node (ref "R41A") (pin "2") (pinfunction "2_2") (pintype "passive"))
      (node (ref "R42") (pin "2") (pinfunction "2_2") (pintype "passive"))
      (node (ref "R43") (pin "2") (pinfunction "2_2") (pintype "passive"))
      (node (ref "R43A") (pin "2") (pinfunction "2_2") (pintype "passive"))
      (node (ref "R44") (pin "2") (pinfunction "2_2") (pintype "passive"))
      (node (ref "R44A") (pin "2") (pinfunction "2_2") (pintype "passive"))
      (node (ref "R45") (pin "2") (pinfunction "2_2") (pintype "passive"))
      (node (ref "R45A") (pin "2") (pinfunction "2_2") (pintype "passive"))
      (node (ref "R46") (pin "2") (pinfunction "2_2") (pintype "passive"))
      (node (ref "R46A") (pin "2") (pinfunction "2_2") (pintype "passive"))
      (node (ref "R47") (pin "2") (pinfunction "2_2") (pintype "passive"))
      (node (ref "R47A") (pin "2") (pinfunction "2_2") (pintype "passive"))
      (node (ref "R48") (pin "2") (pinfunction "2_2") (pintype "passive"))
      (node (ref "R48A") (pin "2") (pinfunction "2_2") (pintype "passive"))
      (node (ref "R49") (pin "2") (pinfunction "2_2") (pintype "passive"))
      (node (ref "R49A") (pin "2") (pinfunction "2_2") (pintype "passive"))
      (node (ref "R50") (pin "1") (pinfunction "1_1") (pintype "passive"))
    )
    (net (code "42") (name "Net-(C15-Pad+)") (class "Default")
      (node (ref "C15") (pin "+") (pinfunction "+_+") (pintype "passive"))
      (node (ref "D22") (pin "A") (pinfunction "A_A") (pintype "passive"))
      (node (ref "R51") (pin "2") (pinfunction "2_2") (pintype "passive"))
      (node (ref "R52") (pin "2") (pinfunction "2_2") (pintype "passive"))
      (node (ref "R53") (pin "2") (pinfunction "2_2") (pintype "passive"))
      (node (ref "R54") (pin "2") (pinfunction "2_2") (pintype "passive"))
      (node (ref "R55A") (pin "2") (pinfunction "2_2") (pintype "passive"))
      (node (ref "R56") (pin "2") (pinfunction "2_2") (pintype "passive"))
      (node (ref "R57") (pin "2") (pinfunction "2_2") (pintype "passive"))
      (node (ref "R58") (pin "2") (pinfunction "2_2") (pintype "passive"))
      (node (ref "R59") (pin "2") (pinfunction "2_2") (pintype "passive"))
      (node (ref "R60A") (pin "2") (pinfunction "2_2") (pintype "passive"))
      (node (ref "R61") (pin "2") (pinfunction "2_2") (pintype "passive"))
      (node (ref "R62") (pin "2") (pinfunction "2_2") (pintype "passive"))
      (node (ref "R62A") (pin "2") (pinfunction "2_2") (pintype "passive"))
      (node (ref "R63") (pin "2") (pinfunction "2_2") (pintype "passive"))
      (node (ref "R64") (pin "2") (pinfunction "2_2") (pintype "passive"))
      (node (ref "R65") (pin "2") (pinfunction "2_2") (pintype "passive"))
      (node (ref "R65A") (pin "2") (pinfunction "2_2") (pintype "passive"))
      (node (ref "R66") (pin "2") (pinfunction "2_2") (pintype "passive"))
    )
    (net (code "43") (name "Net-(C15-Pad-)") (class "Default")
      (node (ref "C15") (pin "-") (pinfunction "-_-") (pintype "passive"))
      (node (ref "R34") (pin "2") (pinfunction "2_2") (pintype "passive"))
    )
    (net (code "44") (name "Net-(D7-PadA)") (class "Default")
      (node (ref "D7") (pin "A") (pinfunction "A_A") (pintype "passive"))
      (node (ref "R37") (pin "1") (pinfunction "1_1") (pintype "passive"))
    )
    (net (code "45") (name "Net-(D21-PadA)") (class "Default")
      (node (ref "D21") (pin "A") (pinfunction "A_A") (pintype "passive"))
      (node (ref "R51") (pin "1") (pinfunction "1_1") (pintype "passive"))
    )
    (net (code "46") (name "Net-(D23-PadA)") (class "Default")
      (node (ref "D23") (pin "A") (pinfunction "A_A") (pintype "passive"))
      (node (ref "R52") (pin "1") (pinfunction "1_1") (pintype "passive"))
    )
    (net (code "47") (name "Net-(D24-PadA)") (class "Default")
      (node (ref "D24") (pin "A") (pinfunction "A_A") (pintype "passive"))
      (node (ref "R53") (pin "1") (pinfunction "1_1") (pintype "passive"))
    )
    (net (code "48") (name "Net-(D25-PadA)") (class "Default")
      (node (ref "D25") (pin "A") (pinfunction "A_A") (pintype "passive"))
      (node (ref "R54") (pin "1") (pinfunction "1_1") (pintype "passive"))
    )
    (net (code "49") (name "Net-(D26-PadA)") (class "Default")
      (node (ref "D26") (pin "A") (pinfunction "A_A") (pintype "passive"))
      (node (ref "R55") (pin "1") (pinfunction "1_1") (pintype "passive"))
    )
    (net (code "50") (name "Net-(D27-PadA)") (class "Default")
      (node (ref "D27") (pin "A") (pinfunction "A_A") (pintype "passive"))
      (node (ref "R56") (pin "1") (pinfunction "1_1") (pintype "passive"))
    )
    (net (code "51") (name "Net-(D28-PadA)") (class "Default")
      (node (ref "D28") (pin "A") (pinfunction "A_A") (pintype "passive"))
      (node (ref "R57") (pin "1") (pinfunction "1_1") (pintype "passive"))
    )
    (net (code "52") (name "Net-(D29-PadA)") (class "Default")
      (node (ref "D29") (pin "A") (pinfunction "A_A") (pintype "passive"))
      (node (ref "R58") (pin "1") (pinfunction "1_1") (pintype "passive"))
    )
    (net (code "53") (name "Net-(D30-PadA)") (class "Default")
      (node (ref "D30") (pin "A") (pinfunction "A_A") (pintype "passive"))
      (node (ref "R59") (pin "1") (pinfunction "1_1") (pintype "passive"))
    )
    (net (code "54") (name "Net-(D31-PadA)") (class "Default")
      (node (ref "D31") (pin "A") (pinfunction "A_A") (pintype "passive"))
      (node (ref "R60") (pin "1") (pinfunction "1_1") (pintype "passive"))
    )
    (net (code "55") (name "Net-(D32-PadA)") (class "Default")
      (node (ref "D32") (pin "A") (pinfunction "A_A") (pintype "passive"))
      (node (ref "R61") (pin "1") (pinfunction "1_1") (pintype "passive"))
    )
    (net (code "56") (name "Net-(D34-PadA)") (class "Default")
      (node (ref "D34") (pin "A") (pinfunction "A_A") (pintype "passive"))
      (node (ref "R63") (pin "1") (pinfunction "1_1") (pintype "passive"))
    )
    (net (code "57") (name "Net-(D35-PadA)") (class "Default")
      (node (ref "D35") (pin "A") (pinfunction "A_A") (pintype "passive"))
      (node (ref "R64") (pin "1") (pinfunction "1_1") (pintype "passive"))
    )
    (net (code "58") (name "Net-(DD1A-I0)") (class "Default")
      (node (ref "DD1") (pin "1") (pinfunction "I0_1") (pintype "input"))
      (node (ref "DD2") (pin "10") (pinfunction "PRE_10") (pintype "input"))
      (node (ref "DD2") (pin "13") (pinfunction "CLR_13") (pintype "input"))
      (node (ref "DD3") (pin "5") (pinfunction "B_5") (pintype "input"))
      (node (ref "R1") (pin "1") (pinfunction "1_1") (pintype "passive"))
      (node (ref "R2") (pin "1") (pinfunction "1_1") (pintype "passive"))
    )
    (net (code "59") (name "Net-(DD1A-O)") (class "Default")
      (node (ref "DD1") (pin "3") (pinfunction "O_3") (pintype "output"))
      (node (ref "DD2") (pin "11") (pinfunction "CLK_11") (pintype "input"))
    )
    (net (code "60") (name "Net-(DD1B-I0)") (class "Default")
      (node (ref "DD1") (pin "4") (pinfunction "I0_4") (pintype "input"))
      (node (ref "DD4") (pin "7") (pinfunction "Y_7") (pintype "output"))
    )
    (net (code "61") (name "Net-(DD1B-I1)") (class "Default")
      (node (ref "DD1") (pin "5") (pinfunction "I1_5") (pintype "input"))
      (node (ref "DD4") (pin "10") (pinfunction "Y_10") (pintype "output"))
    )
    (net (code "62") (name "Net-(DD1B-O)") (class "Default")
      (node (ref "DD1") (pin "10") (pinfunction "I1_10") (pintype "input"))
      (node (ref "DD1") (pin "6") (pinfunction "O_6") (pintype "output"))
    )
    (net (code "63") (name "Net-(DD1C-O)") (class "Default")
      (node (ref "DD1") (pin "8") (pinfunction "O_8") (pintype "output"))
      (node (ref "R29") (pin "1") (pinfunction "1_1") (pintype "passive"))
    )
    (net (code "64") (name "Net-(DD1D-O)") (class "Default")
      (node (ref "C2") (pin "1") (pinfunction "1_1") (pintype "passive"))
      (node (ref "DD1") (pin "11") (pinfunction "O_11") (pintype "output"))
      (node (ref "DD3") (pin "3") (pinfunction "A1_3") (pintype "input"))
      (node (ref "DD3") (pin "4") (pinfunction "A2_4") (pintype "input"))
    )
    (net (code "65") (name "Net-(DD2A-CLK)") (class "Default")
      (node (ref "DD2") (pin "3") (pinfunction "CLK_3") (pintype "input"))
      (node (ref "DD3") (pin "1") (pinfunction "~{Q}_1") (pintype "output"))
    )
    (net (code "66") (name "Net-(DD2A-CLR)") (class "Default")
      (node (ref "C4") (pin "2") (pinfunction "2_2") (pintype "passive"))
      (node (ref "DD2") (pin "1") (pinfunction "CLR_1") (pintype "input"))
      (node (ref "R15") (pin "1") (pinfunction "1_1") (pintype "passive"))
    )
    (net (code "67") (name "Net-(DD2A-D)") (class "Default")
      (node (ref "DD2") (pin "2") (pinfunction "D_2") (pintype "input"))
      (node (ref "DD2") (pin "6") (pinfunction "~{Q}_6") (pintype "output"))
      (node (ref "DD4") (pin "6") (pinfunction "EN_6") (pintype "input"))
      (node (ref "R15") (pin "2") (pinfunction "2_2") (pintype "passive"))
    )
    (net (code "68") (name "Net-(DD2A-PRE)") (class "Default")
      (node (ref "DD2") (pin "4") (pinfunction "PRE_4") (pintype "input"))
      (node (ref "DD3") (pin "9") (pinfunction "R_9") (pintype "input"))
      (node (ref "R2") (pin "2") (pinfunction "2_2") (pintype "passive"))
    )
    (net (code "69") (name "Net-(DD2A-Q)") (class "Default")
      (node (ref "DD2") (pin "5") (pinfunction "Q_5") (pintype "output"))
      (node (ref "DD4") (pin "11") (pinfunction "EN_11") (pintype "input"))
    )
    (net (code "70") (name "Net-(DD2B-Q)") (class "Default")
      (node (ref "DD2") (pin "9") (pinfunction "Q_9") (pintype "output"))
      (node (ref "R11") (pin "3") (pinfunction "A_3") (pintype "passive"))
      (node (ref "R13") (pin "3") (pinfunction "A_3") (pintype "passive"))
    )
    (net (code "71") (name "Net-(DD3A-C)") (class "Default")
      (node (ref "C3") (pin "1") (pinfunction "1_1") (pintype "passive"))
      (node (ref "DD3") (pin "10") (pinfunction "C_10") (pintype "input"))
    )
    (net (code "72") (name "Net-(DD3A-R{slash}C)") (class "Default")
      (node (ref "C3") (pin "2") (pinfunction "2_2") (pintype "passive"))
      (node (ref "DD3") (pin "11") (pinfunction "R/C_11") (pintype "input"))
    )
    (net (code "73") (name "Net-(DD4A-FC)") (class "Default")
      (node (ref "D3") (pin "C") (pinfunction "C_C") (pintype "passive"))
      (node (ref "D4") (pin "C") (pinfunction "C_C") (pintype "passive"))
      (node (ref "DD4") (pin "2") (pinfunction "FC_2") (pintype "input"))
    )
    (net (code "74") (name "Net-(DD4A-RNG)") (class "Default")
      (node (ref "DD4") (pin "3") (pinfunction "RNG_3") (pintype "input"))
      (node (ref "R16") (pin "2") (pinfunction "2_2") (pintype "passive"))
      (node (ref "R17") (pin "1") (pinfunction "1_1") (pintype "passive"))
    )
    (net (code "75") (name "Net-(DD4B-FC)") (class "Default")
      (node (ref "DD4") (pin "1") (pinfunction "FC_1") (pintype "input"))
      (node (ref "R10") (pin "1") (pinfunction "1_1") (pintype "passive"))
      (node (ref "VT3") (pin "E") (pinfunction "E_E") (pintype "passive"))
    )
    (net (code "76") (name "Net-(DD4B-RNG)") (class "Default")
      (node (ref "D1") (pin "C") (pinfunction "C_C") (pintype "passive"))
      (node (ref "D2") (pin "C") (pinfunction "C_C") (pintype "passive"))
      (node (ref "DD4") (pin "14") (pinfunction "RNG_14") (pintype "input"))
    )
    (net (code "77") (name "Net-(DD4C-OSCGND)") (class "Default")
      (node (ref "DD4") (pin "8") (pinfunction "OSCGND_8") (pintype "power_in"))
      (node (ref "J2") (pin "2") (pinfunction "2_2") (pintype "passive"))
    )
    (net (code "78") (name "Net-(DD4C-OSCVCC)") (class "Default")
      (node (ref "DD4") (pin "15") (pinfunction "OSCVCC_15") (pintype "power_in"))
      (node (ref "J1") (pin "2") (pinfunction "2_2") (pintype "passive"))
    )
    (net (code "79") (name "Net-(DD5A-0)") (class "Default")
      (node (ref "D5") (pin "C") (pinfunction "C_C") (pintype "passive"))
      (node (ref "DD5") (pin "1") (pinfunction "0_1") (pintype "output"))
    )
    (net (code "80") (name "Net-(DD5A-1)") (class "Default")
      (node (ref "D6") (pin "C") (pinfunction "C_C") (pintype "passive"))
      (node (ref "DD5") (pin "2") (pinfunction "1_2") (pintype "output"))
    )
    (net (code "81") (name "Net-(DD5A-2)") (class "Default")
      (node (ref "D7") (pin "C") (pinfunction "C_C") (pintype "passive"))
      (node (ref "DD5") (pin "3") (pinfunction "2_3") (pintype "output"))
    )
    (net (code "82") (name "Net-(DD5A-3)") (class "Default")
      (node (ref "D8") (pin "C") (pinfunction "C_C") (pintype "passive"))
      (node (ref "DD5") (pin "4") (pinfunction "3_4") (pintype "output"))
    )
    (net (code "83") (name "Net-(DD5A-4)") (class "Default")
      (node (ref "D9") (pin "C") (pinfunction "C_C") (pintype "passive"))
      (node (ref "DD5") (pin "5") (pinfunction "4_5") (pintype "output"))
    )
    (net (code "84") (name "Net-(DD5A-5)") (class "Default")
      (node (ref "D10") (pin "C") (pinfunction "C_C") (pintype "passive"))
      (node (ref "DD5") (pin "6") (pinfunction "5_6") (pintype "output"))
    )
    (net (code "85") (name "Net-(DD5A-6)") (class "Default")
      (node (ref "D11") (pin "C") (pinfunction "C_C") (pintype "passive"))
      (node (ref "DD5") (pin "7") (pinfunction "6_7") (pintype "output"))
    )
    (net (code "86") (name "Net-(DD5A-7)") (class "Default")
      (node (ref "D12") (pin "C") (pinfunction "C_C") (pintype "passive"))
      (node (ref "DD5") (pin "8") (pinfunction "7_8") (pintype "output"))
    )
    (net (code "87") (name "Net-(DD5A-8)") (class "Default")
      (node (ref "D13") (pin "C") (pinfunction "C_C") (pintype "passive"))
      (node (ref "DD5") (pin "9") (pinfunction "8_9") (pintype "output"))
    )
    (net (code "88") (name "Net-(DD5A-9)") (class "Default")
      (node (ref "D14") (pin "C") (pinfunction "C_C") (pintype "passive"))
      (node (ref "DD5") (pin "10") (pinfunction "9_10") (pintype "output"))
    )
    (net (code "89") (name "Net-(DD5A-10)") (class "Default")
      (node (ref "D15") (pin "C") (pinfunction "C_C") (pintype "passive"))
      (node (ref "DD5") (pin "11") (pinfunction "10_11") (pintype "output"))
    )
    (net (code "90") (name "Net-(DD5A-11)") (class "Default")
      (node (ref "D16") (pin "C") (pinfunction "C_C") (pintype "passive"))
      (node (ref "DD5") (pin "13") (pinfunction "11_13") (pintype "output"))
    )
    (net (code "91") (name "Net-(DD5A-12)") (class "Default")
      (node (ref "D17") (pin "C") (pinfunction "C_C") (pintype "passive"))
      (node (ref "DD5") (pin "14") (pinfunction "12_14") (pintype "output"))
    )
    (net (code "92") (name "Net-(DD5A-13)") (class "Default")
      (node (ref "D18") (pin "C") (pinfunction "C_C") (pintype "passive"))
      (node (ref "DD5") (pin "15") (pinfunction "13_15") (pintype "output"))
    )
    (net (code "93") (name "Net-(DD5A-14)") (class "Default")
      (node (ref "D19") (pin "C") (pinfunction "C_C") (pintype "passive"))
      (node (ref "DD5") (pin "16") (pinfunction "14_16") (pintype "output"))
    )
    (net (code "94") (name "Net-(DD5A-15)") (class "Default")
      (node (ref "D20") (pin "C") (pinfunction "C_C") (pintype "passive"))
      (node (ref "DD5") (pin "17") (pinfunction "15_17") (pintype "output"))
    )
    (net (code "95") (name "Net-(DD6A-0)") (class "Default")
      (node (ref "D21") (pin "C") (pinfunction "C_C") (pintype "passive"))
      (node (ref "DD6") (pin "1") (pinfunction "0_1") (pintype "output"))
    )
    (net (code "96") (name "Net-(DD6A-1)") (class "Default")
      (node (ref "D22") (pin "C") (pinfunction "C_C") (pintype "passive"))
      (node (ref "DD6") (pin "2") (pinfunction "1_2") (pintype "output"))
    )
    (net (code "97") (name "Net-(DD6A-2)") (class "Default")
      (node (ref "D23") (pin "C") (pinfunction "C_C") (pintype "passive"))
      (node (ref "DD6") (pin "3") (pinfunction "2_3") (pintype "output"))
    )
    (net (code "98") (name "Net-(DD6A-3)") (class "Default")
      (node (ref "D24") (pin "C") (pinfunction "C_C") (pintype "passive"))
      (node (ref "DD6") (pin "4") (pinfunction "3_4") (pintype "output"))
    )
    (net (code "99") (name "Net-(DD6A-4)") (class "Default")
      (node (ref "D25") (pin "C") (pinfunction "C_C") (pintype "passive"))
      (node (ref "DD6") (pin "5") (pinfunction "4_5") (pintype "output"))
    )
    (net (code "100") (name "Net-(DD6A-5)") (class "Default")
      (node (ref "D26") (pin "C") (pinfunction "C_C") (pintype "passive"))
      (node (ref "DD6") (pin "6") (pinfunction "5_6") (pintype "output"))
    )
    (net (code "101") (name "Net-(DD6A-6)") (class "Default")
      (node (ref "D27") (pin "C") (pinfunction "C_C") (pintype "passive"))
      (node (ref "DD6") (pin "7") (pinfunction "6_7") (pintype "output"))
    )
    (net (code "102") (name "Net-(DD6A-7)") (class "Default")
      (node (ref "D28") (pin "C") (pinfunction "C_C") (pintype "passive"))
      (node (ref "DD6") (pin "8") (pinfunction "7_8") (pintype "output"))
    )
    (net (code "103") (name "Net-(DD6A-8)") (class "Default")
      (node (ref "D29") (pin "C") (pinfunction "C_C") (pintype "passive"))
      (node (ref "DD6") (pin "9") (pinfunction "8_9") (pintype "output"))
    )
    (net (code "104") (name "Net-(DD6A-9)") (class "Default")
      (node (ref "D30") (pin "C") (pinfunction "C_C") (pintype "passive"))
      (node (ref "DD6") (pin "10") (pinfunction "9_10") (pintype "output"))
    )
    (net (code "105") (name "Net-(DD6A-10)") (class "Default")
      (node (ref "D31") (pin "C") (pinfunction "C_C") (pintype "passive"))
      (node (ref "DD6") (pin "11") (pinfunction "10_11") (pintype "output"))
    )
    (net (code "106") (name "Net-(DD6A-11)") (class "Default")
      (node (ref "D32") (pin "C") (pinfunction "C_C") (pintype "passive"))
      (node (ref "DD6") (pin "13") (pinfunction "11_13") (pintype "output"))
    )
    (net (code "107") (name "Net-(DD6A-12)") (class "Default")
      (node (ref "D33") (pin "C") (pinfunction "C_C") (pintype "passive"))
      (node (ref "DD6") (pin "14") (pinfunction "12_14") (pintype "output"))
    )
    (net (code "108") (name "Net-(DD6A-13)") (class "Default")
      (node (ref "D34") (pin "C") (pinfunction "C_C") (pintype "passive"))
      (node (ref "DD6") (pin "15") (pinfunction "13_15") (pintype "output"))
    )
    (net (code "109") (name "Net-(DD6A-14)") (class "Default")
      (node (ref "D35") (pin "C") (pinfunction "C_C") (pintype "passive"))
      (node (ref "DD6") (pin "16") (pinfunction "14_16") (pintype "output"))
    )
    (net (code "110") (name "Net-(DD6A-15)") (class "Default")
      (node (ref "D36") (pin "C") (pinfunction "C_C") (pintype "passive"))
      (node (ref "DD6") (pin "17") (pinfunction "15_17") (pintype "output"))
    )
    (net (code "111") (name "Net-(L-Pad2)") (class "Default")
      (node (ref "L") (pin "2") (pinfunction "2_2") (pintype "bidirectional"))
      (node (ref "R34") (pin "1") (pinfunction "1_1") (pintype "passive"))
    )
    (net (code "112") (name "Net-(R5-Pad1)") (class "Default")
      (node (ref "R5") (pin "1") (pinfunction "1_1") (pintype "passive"))
      (node (ref "VT1") (pin "C") (pinfunction "C_C") (pintype "passive"))
      (node (ref "VT2") (pin "B") (pinfunction "B_B") (pintype "passive"))
    )
    (net (code "113") (name "Net-(R6-Pad2)") (class "Default")
      (node (ref "R6") (pin "2") (pinfunction "2_2") (pintype "passive"))
      (node (ref "R7") (pin "1") (pinfunction "1_1") (pintype "passive"))
      (node (ref "VT1") (pin "E") (pinfunction "E_E") (pintype "passive"))
    )
    (net (code "114") (name "Net-(R7-Pad2)") (class "Default")
      (node (ref "R7") (pin "2") (pinfunction "2_2") (pintype "passive"))
      (node (ref "R9") (pin "2") (pinfunction "2_2") (pintype "passive"))
      (node (ref "VT2") (pin "C") (pinfunction "C_C") (pintype "passive"))
      (node (ref "VT3") (pin "B") (pinfunction "B_B") (pintype "passive"))
    )
    (net (code "115") (name "Net-(R8-Pad1)") (class "Default")
      (node (ref "R8") (pin "1") (pinfunction "1_1") (pintype "passive"))
      (node (ref "VT2") (pin "E") (pinfunction "E_E") (pintype "passive"))
    )
    (net (code "116") (name "Net-(R11-S)") (class "Default")
      (node (ref "D1") (pin "A") (pinfunction "A_A") (pintype "passive"))
      (node (ref "R11") (pin "2") (pinfunction "S_2") (pintype "passive"))
    )
    (net (code "117") (name "Net-(R12-S)") (class "Default")
      (node (ref "D2") (pin "A") (pinfunction "A_A") (pintype "passive"))
      (node (ref "R12") (pin "2") (pinfunction "S_2") (pintype "passive"))
    )
    (net (code "118") (name "Net-(R13-S)") (class "Default")
      (node (ref "D3") (pin "A") (pinfunction "A_A") (pintype "passive"))
      (node (ref "R13") (pin "2") (pinfunction "S_2") (pintype "passive"))
    )
    (net (code "119") (name "Net-(R14-S)") (class "Default")
      (node (ref "D4") (pin "A") (pinfunction "A_A") (pintype "passive"))
      (node (ref "R14") (pin "2") (pinfunction "S_2") (pintype "passive"))
    )
    (net (code "120") (name "Net-(R20-Pad1)") (class "Default")
      (node (ref "R20") (pin "1") (pinfunction "1_1") (pintype "passive"))
      (node (ref "VT4") (pin "C") (pinfunction "C_C") (pintype "passive"))
      (node (ref "VT5") (pin "B") (pinfunction "B_B") (pintype "passive"))
    )
    (net (code "121") (name "Net-(R21-Pad2)") (class "Default")
      (node (ref "R21") (pin "2") (pinfunction "2_2") (pintype "passive"))
      (node (ref "R22") (pin "1") (pinfunction "1_1") (pintype "passive"))
      (node (ref "R23") (pin "1") (pinfunction "1_1") (pintype "passive"))
      (node (ref "VT4") (pin "E") (pinfunction "E_E") (pintype "passive"))
    )
    (net (code "122") (name "Net-(R22-Pad2)") (class "Default")
      (node (ref "R22") (pin "2") (pinfunction "2_2") (pintype "passive"))
      (node (ref "R25") (pin "2") (pinfunction "2_2") (pintype "passive"))
      (node (ref "R26") (pin "1") (pinfunction "1_1") (pintype "passive"))
      (node (ref "VT5") (pin "C") (pinfunction "C_C") (pintype "passive"))
    )
    (net (code "123") (name "Net-(R24-Pad1)") (class "Default")
      (node (ref "R24") (pin "1") (pinfunction "1_1") (pintype "passive"))
      (node (ref "VT5") (pin "E") (pinfunction "E_E") (pintype "passive"))
    )
    (net (code "124") (name "Net-(R28-A)") (class "Default")
      (node (ref "R27") (pin "1") (pinfunction "1_1") (pintype "passive"))
      (node (ref "R28") (pin "3") (pinfunction "A_3") (pintype "passive"))
      (node (ref "R29") (pin "2") (pinfunction "2_2") (pintype "passive"))
    )
    (net (code "125") (name "Net-(R28-S)") (class "Default")
      (node (ref "C9") (pin "1") (pinfunction "1_1") (pintype "passive"))
      (node (ref "R28") (pin "2") (pinfunction "S_2") (pintype "passive"))
    )
    (net (code "126") (name "Net-(R37-Pad2)") (class "Default")
      (node (ref "R37") (pin "2") (pinfunction "2_2") (pintype "passive"))
      (node (ref "R37A") (pin "1") (pinfunction "1_1") (pintype "passive"))
    )
    (net (code "127") (name "Net-(R40-Pad2)") (class "Default")
      (node (ref "R40") (pin "2") (pinfunction "2_2") (pintype "passive"))
      (node (ref "R40A") (pin "1") (pinfunction "1_1") (pintype "passive"))
    )
    (net (code "128") (name "Net-(R55-Pad2)") (class "Default")
      (node (ref "R55") (pin "2") (pinfunction "2_2") (pintype "passive"))
      (node (ref "R55A") (pin "1") (pinfunction "1_1") (pintype "passive"))
    )
    (net (code "129") (name "Net-(R60-Pad2)") (class "Default")
      (node (ref "R60") (pin "2") (pinfunction "2_2") (pintype "passive"))
      (node (ref "R60A") (pin "1") (pinfunction "1_1") (pintype "passive"))
    )
    (net (code "130") (name "unconnected-(DD3A-Q-Pad6)") (class "Default")
      (node (ref "DD3") (pin "6") (pinfunction "Q_6") (pintype "output"))
    )
    (net (code "131") (name "unconnected-(SV1-Pad1)") (class "Default")
      (node (ref "SV1") (pin "1") (pinfunction "1_1") (pintype "passive"))
    )
  )
)
